# fCPU_Controller1.net
KiCad netlist of a schematic drawn in EAGLE
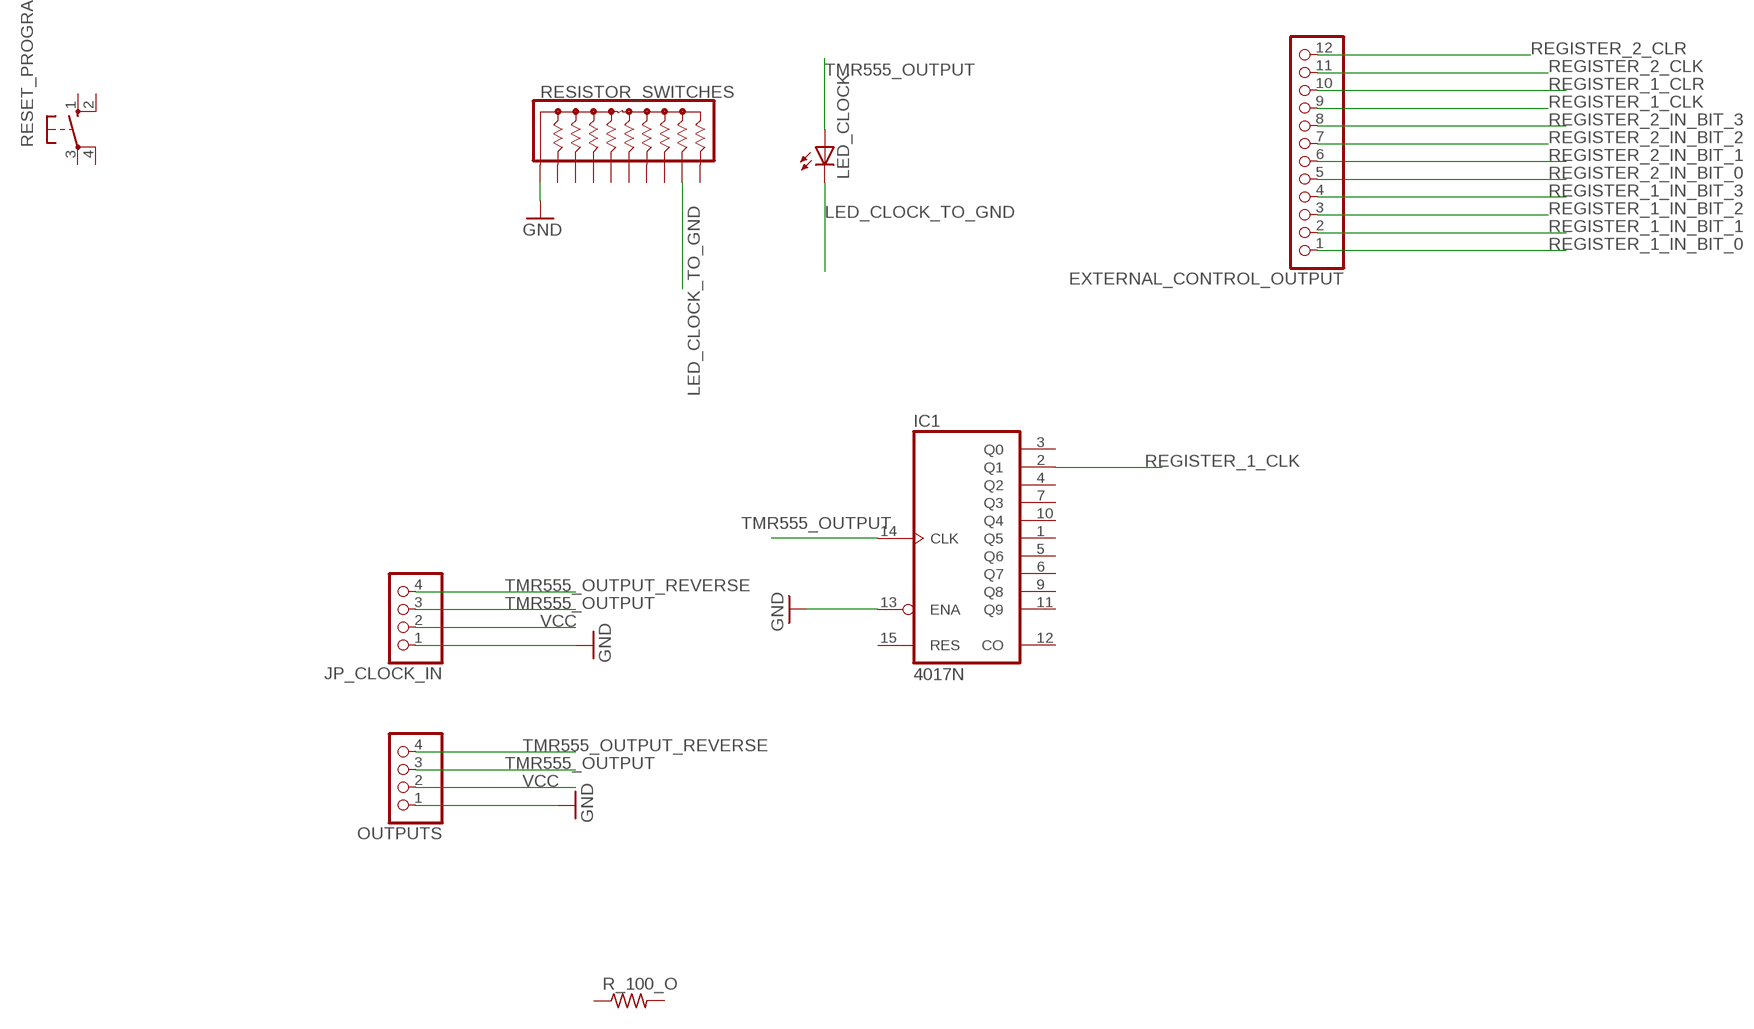
[diagram p0: schematic, sheet 1]

(export (version "E")
  (design (tool "Eeschema 10.0.6"))
  (components
    (comp (ref "EXTERNAL_CONTROL_OUTPUT")
      (value "PINHD-1X12")
      (footprint "eagle-import:1X12")
      (libsource (lib "eagle-import") (part "PINHD-1X12"))
    )
    (comp (ref "IC1")
      (value "4017N")
      (footprint "eagle-import:DIL16")
      (libsource (lib "eagle-import") (part "4017N"))
    )
    (comp (ref "JP_CLOCK_IN")
      (value "PINHD-1X4")
      (footprint "eagle-import:1X04")
      (libsource (lib "eagle-import") (part "PINHD-1X4"))
    )
    (comp (ref "LED_CLOCK")
      (value "LEDSMT1206")
      (footprint "eagle-import:1206")
      (libsource (lib "eagle-import") (part "LEDSMT1206"))
    )
    (comp (ref "OUTPUTS")
      (value "PINHD-1X4")
      (footprint "eagle-import:1X04")
      (libsource (lib "eagle-import") (part "PINHD-1X4"))
    )
    (comp (ref "RESET_PROGRAM")
      (value "10-XX")
      (footprint "eagle-import:B3F-10XX")
      (fields (field (name "MPN") "B3F-1000"))
      (libsource (lib "eagle-import") (part "10-XX"))
    )
    (comp (ref "RESISTOR_SWITCHES")
      (value "4610X")
      (footprint "eagle-import:SIP10")
      (libsource (lib "eagle-import") (part "4610X"))
    )
    (comp (ref "R_100_O")
      (value "R-US_R1206")
      (footprint "eagle-import:R1206")
      (libsource (lib "eagle-import") (part "R-US_R1206"))
    )
  )
  (nets
    (net (code "1") (name "/LED_CLOCK_TO_GND") (class "Default")
      (node (ref "LED_CLOCK") (pin "C") (pinfunction "C_C") (pintype "passive"))
      (node (ref "RESISTOR_SWITCHES") (pin "9") (pinfunction "9_9") (pintype "passive"))
    )
    (net (code "2") (name "/REGISTER_1_CLK") (class "Default")
      (node (ref "EXTERNAL_CONTROL_OUTPUT") (pin "9") (pinfunction "9_9") (pintype "passive"))
      (node (ref "IC1") (pin "2") (pinfunction "Q1_2") (pintype "output"))
    )
    (net (code "3") (name "/REGISTER_1_CLR") (class "Default")
      (node (ref "EXTERNAL_CONTROL_OUTPUT") (pin "10") (pinfunction "10_10") (pintype "passive"))
    )
    (net (code "4") (name "/REGISTER_1_IN_BIT_0") (class "Default")
      (node (ref "EXTERNAL_CONTROL_OUTPUT") (pin "1") (pinfunction "1_1") (pintype "passive"))
    )
    (net (code "5") (name "/REGISTER_1_IN_BIT_1") (class "Default")
      (node (ref "EXTERNAL_CONTROL_OUTPUT") (pin "2") (pinfunction "2_2") (pintype "passive"))
    )
    (net (code "6") (name "/REGISTER_1_IN_BIT_2") (class "Default")
      (node (ref "EXTERNAL_CONTROL_OUTPUT") (pin "3") (pinfunction "3_3") (pintype "passive"))
    )
    (net (code "7") (name "/REGISTER_1_IN_BIT_3") (class "Default")
      (node (ref "EXTERNAL_CONTROL_OUTPUT") (pin "4") (pinfunction "4_4") (pintype "passive"))
    )
    (net (code "8") (name "/REGISTER_2_CLK") (class "Default")
      (node (ref "EXTERNAL_CONTROL_OUTPUT") (pin "11") (pinfunction "11_11") (pintype "passive"))
    )
    (net (code "9") (name "/REGISTER_2_CLR") (class "Default")
      (node (ref "EXTERNAL_CONTROL_OUTPUT") (pin "12") (pinfunction "12_12") (pintype "passive"))
    )
    (net (code "10") (name "/REGISTER_2_IN_BIT_0") (class "Default")
      (node (ref "EXTERNAL_CONTROL_OUTPUT") (pin "5") (pinfunction "5_5") (pintype "passive"))
    )
    (net (code "11") (name "/REGISTER_2_IN_BIT_1") (class "Default")
      (node (ref "EXTERNAL_CONTROL_OUTPUT") (pin "6") (pinfunction "6_6") (pintype "passive"))
    )
    (net (code "12") (name "/REGISTER_2_IN_BIT_2") (class "Default")
      (node (ref "EXTERNAL_CONTROL_OUTPUT") (pin "7") (pinfunction "7_7") (pintype "passive"))
    )
    (net (code "13") (name "/REGISTER_2_IN_BIT_3") (class "Default")
      (node (ref "EXTERNAL_CONTROL_OUTPUT") (pin "8") (pinfunction "8_8") (pintype "passive"))
    )
    (net (code "14") (name "/TMR555_OUTPUT") (class "Default")
      (node (ref "IC1") (pin "14") (pinfunction "CLK_14") (pintype "input"))
      (node (ref "JP_CLOCK_IN") (pin "3") (pinfunction "3_3") (pintype "passive"))
      (node (ref "LED_CLOCK") (pin "A") (pinfunction "A_A") (pintype "passive"))
      (node (ref "OUTPUTS") (pin "3") (pinfunction "3_3") (pintype "passive"))
    )
    (net (code "15") (name "/TMR555_OUTPUT_REVERSE") (class "Default")
      (node (ref "JP_CLOCK_IN") (pin "4") (pinfunction "4_4") (pintype "passive"))
      (node (ref "OUTPUTS") (pin "4") (pinfunction "4_4") (pintype "passive"))
    )
    (net (code "16") (name "/VCC") (class "Default")
      (node (ref "JP_CLOCK_IN") (pin "2") (pinfunction "2_2") (pintype "passive"))
      (node (ref "OUTPUTS") (pin "2") (pinfunction "2_2") (pintype "passive"))
    )
    (net (code "17") (name "GND") (class "Default")
      (node (ref "IC1") (pin "13") (pinfunction "ENA_13") (pintype "input"))
      (node (ref "JP_CLOCK_IN") (pin "1") (pinfunction "1_1") (pintype "passive"))
      (node (ref "OUTPUTS") (pin "1") (pinfunction "1_1") (pintype "passive"))
      (node (ref "RESISTOR_SWITCHES") (pin "1") (pinfunction "1_1") (pintype "passive"))
    )
    (net (code "18") (name "unconnected-(IC1A-CO-Pad12)") (class "Default")
      (node (ref "IC1") (pin "12") (pinfunction "CO_12") (pintype "output"))
    )
    (net (code "19") (name "unconnected-(IC1A-Q0-Pad3)") (class "Default")
      (node (ref "IC1") (pin "3") (pinfunction "Q0_3") (pintype "output"))
    )
    (net (code "20") (name "unconnected-(IC1A-Q2-Pad4)") (class "Default")
      (node (ref "IC1") (pin "4") (pinfunction "Q2_4") (pintype "output"))
    )
    (net (code "21") (name "unconnected-(IC1A-Q3-Pad7)") (class "Default")
      (node (ref "IC1") (pin "7") (pinfunction "Q3_7") (pintype "output"))
    )
    (net (code "22") (name "unconnected-(IC1A-Q4-Pad10)") (class "Default")
      (node (ref "IC1") (pin "10") (pinfunction "Q4_10") (pintype "output"))
    )
    (net (code "23") (name "unconnected-(IC1A-Q5-Pad1)") (class "Default")
      (node (ref "IC1") (pin "1") (pinfunction "Q5_1") (pintype "output"))
    )
    (net (code "24") (name "unconnected-(IC1A-Q6-Pad5)") (class "Default")
      (node (ref "IC1") (pin "5") (pinfunction "Q6_5") (pintype "output"))
    )
    (net (code "25") (name "unconnected-(IC1A-Q7-Pad6)") (class "Default")
      (node (ref "IC1") (pin "6") (pinfunction "Q7_6") (pintype "output"))
    )
    (net (code "26") (name "unconnected-(IC1A-Q8-Pad9)") (class "Default")
      (node (ref "IC1") (pin "9") (pinfunction "Q8_9") (pintype "output"))
    )
    (net (code "27") (name "unconnected-(IC1A-Q9-Pad11)") (class "Default")
      (node (ref "IC1") (pin "11") (pinfunction "Q9_11") (pintype "output"))
    )
    (net (code "28") (name "unconnected-(IC1A-RES-Pad15)") (class "Default")
      (node (ref "IC1") (pin "15") (pinfunction "RES_15") (pintype "input"))
    )
    (net (code "29") (name "unconnected-(RESET_PROGRAM-P-Pad3)") (class "Default")
      (node (ref "RESET_PROGRAM") (pin "3") (pinfunction "P_3") (pintype "passive"))
    )
    (net (code "30") (name "unconnected-(RESET_PROGRAM-P1-Pad4)") (class "Default")
      (node (ref "RESET_PROGRAM") (pin "4") (pinfunction "P1_4") (pintype "passive"))
    )
    (net (code "31") (name "unconnected-(RESET_PROGRAM-S-Pad1)") (class "Default")
      (node (ref "RESET_PROGRAM") (pin "1") (pinfunction "S_1") (pintype "passive"))
    )
    (net (code "32") (name "unconnected-(RESET_PROGRAM-S1-Pad2)") (class "Default")
      (node (ref "RESET_PROGRAM") (pin "2") (pinfunction "S1_2") (pintype "passive"))
    )
    (net (code "33") (name "unconnected-(RESISTOR_SWITCHES-Pad2)") (class "Default")
      (node (ref "RESISTOR_SWITCHES") (pin "2") (pinfunction "2_2") (pintype "passive"))
    )
    (net (code "34") (name "unconnected-(RESISTOR_SWITCHES-Pad3)") (class "Default")
      (node (ref "RESISTOR_SWITCHES") (pin "3") (pinfunction "3_3") (pintype "passive"))
    )
    (net (code "35") (name "unconnected-(RESISTOR_SWITCHES-Pad4)") (class "Default")
      (node (ref "RESISTOR_SWITCHES") (pin "4") (pinfunction "4_4") (pintype "passive"))
    )
    (net (code "36") (name "unconnected-(RESISTOR_SWITCHES-Pad5)") (class "Default")
      (node (ref "RESISTOR_SWITCHES") (pin "5") (pinfunction "5_5") (pintype "passive"))
    )
    (net (code "37") (name "unconnected-(RESISTOR_SWITCHES-Pad6)") (class "Default")
      (node (ref "RESISTOR_SWITCHES") (pin "6") (pinfunction "6_6") (pintype "passive"))
    )
    (net (code "38") (name "unconnected-(RESISTOR_SWITCHES-Pad7)") (class "Default")
      (node (ref "RESISTOR_SWITCHES") (pin "7") (pinfunction "7_7") (pintype "passive"))
    )
    (net (code "39") (name "unconnected-(RESISTOR_SWITCHES-Pad8)") (class "Default")
      (node (ref "RESISTOR_SWITCHES") (pin "8") (pinfunction "8_8") (pintype "passive"))
    )
    (net (code "40") (name "unconnected-(RESISTOR_SWITCHES-Pad10)") (class "Default")
      (node (ref "RESISTOR_SWITCHES") (pin "10") (pinfunction "10_10") (pintype "passive"))
    )
    (net (code "41") (name "unconnected-(R_100_O-Pad1)") (class "Default")
      (node (ref "R_100_O") (pin "1") (pinfunction "1_1") (pintype "passive"))
    )
    (net (code "42") (name "unconnected-(R_100_O-Pad2)") (class "Default")
      (node (ref "R_100_O") (pin "2") (pinfunction "2_2") (pintype "passive"))
    )
  )
)
